# bat_mini_drby_viii.net
KiCad netlist of a schematic drawn in EAGLE
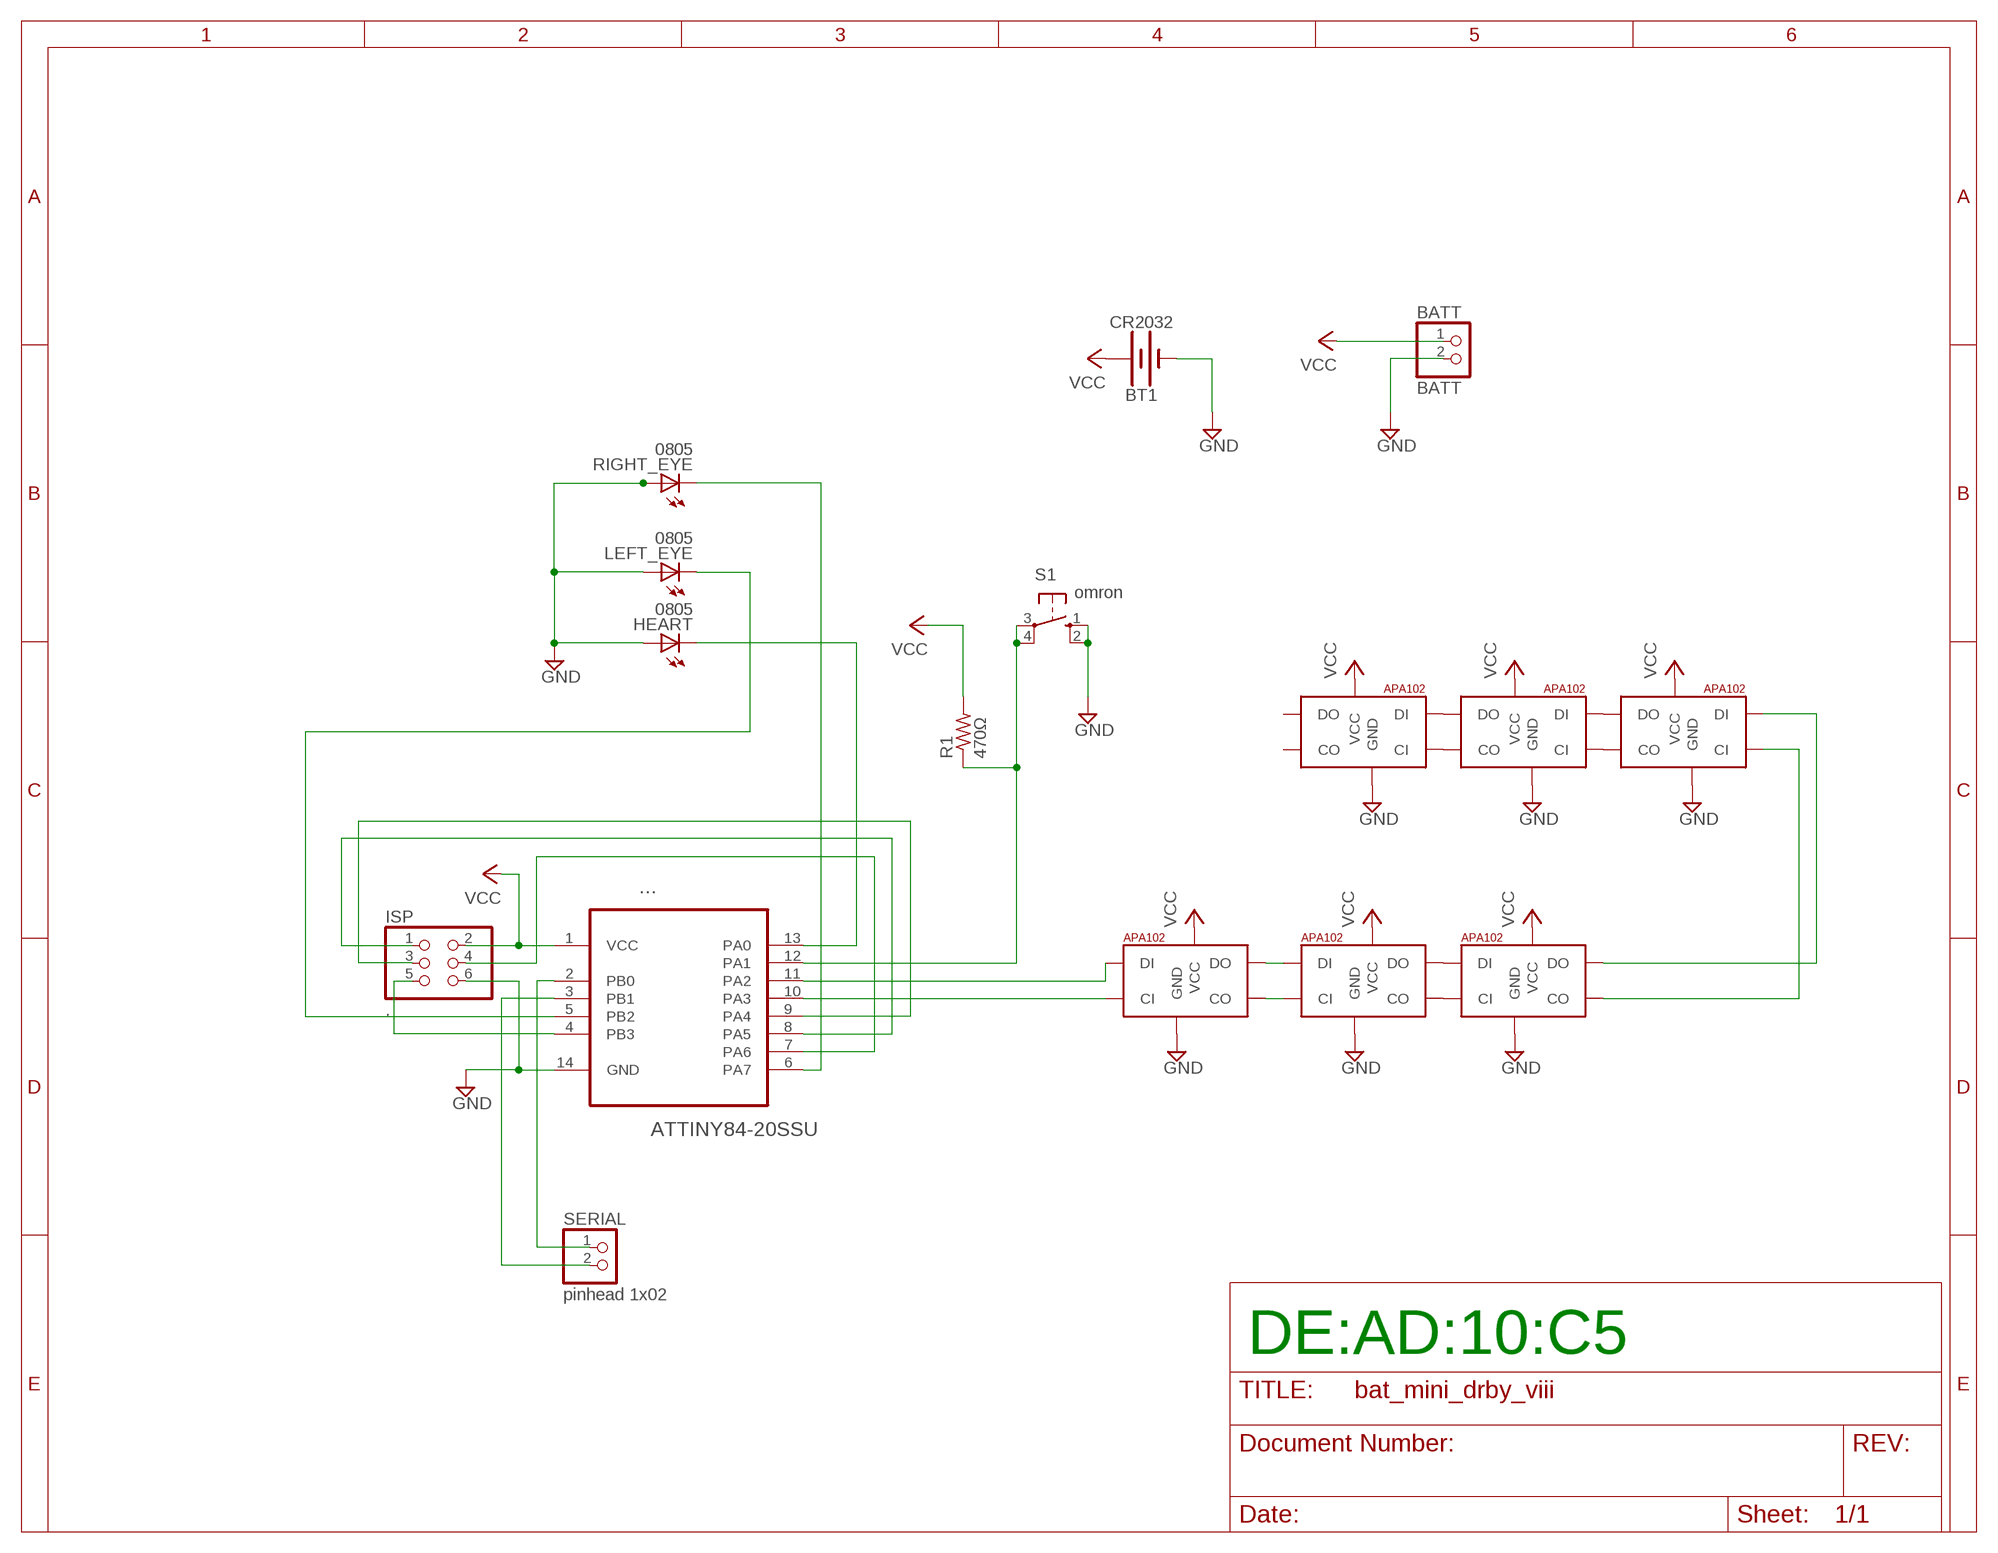
[diagram p0: schematic, sheet 1]

(export (version "E")
  (design (tool "Eeschema 10.0.6"))
  (components
    (comp (ref "...")
      (value "ATTINY84-20SSU")
      (footprint "eagle-import:SOIC127P600X175-14N")
      (libsource (lib "eagle-import") (part "ATTINY84-20SSU"))
    )
    (comp (ref "BATT")
      (value "BATT")
      (footprint "eagle-import:1X02")
      (libsource (lib "eagle-import") (part "PINHD-1X2"))
    )
    (comp (ref "BT1")
      (value "CR2032")
      (footprint "eagle-import:BATTCON_20MM_4LEGS")
      (libsource (lib "eagle-import") (part "BATTERY-20MM_SMD_4LEGS"))
    )
    (comp (ref "HEART")
      (value "0805")
      (footprint "eagle-import:CHIP-LED0805")
      (libsource (lib "eagle-import") (part "LEDCHIP-LED0805"))
    )
    (comp (ref "ISP")
      (value ".")
      (footprint "eagle-import:2X03")
      (libsource (lib "eagle-import") (part "PINHD-2X3"))
    )
    (comp (ref "LEFT_EYE")
      (value "0805")
      (footprint "eagle-import:CHIP-LED0805")
      (libsource (lib "eagle-import") (part "LEDCHIP-LED0805"))
    )
    (comp (ref "R1")
      (value "470Ω")
      (footprint "eagle-import:R0805")
      (libsource (lib "eagle-import") (part "R-US_R0805"))
    )
    (comp (ref "RIGHT_EYE")
      (value "0805")
      (footprint "eagle-import:CHIP-LED0805")
      (libsource (lib "eagle-import") (part "LEDCHIP-LED0805"))
    )
    (comp (ref "S1")
      (value "omron")
      (footprint "eagle-import:B3F-10XX")
      (fields (field (name "MPN") "B3F-1000"))
      (libsource (lib "eagle-import") (part "10-XX"))
    )
    (comp (ref "SERIAL")
      (value "pinhead 1x02")
      (footprint "eagle-import:1X02")
      (libsource (lib "eagle-import") (part "PINHD-1X2"))
    )
    (comp (ref "U$1")
      (value "APA1025050")
      (footprint "eagle-import:APA102_5050")
      (libsource (lib "eagle-import") (part "APA1025050"))
    )
    (comp (ref "U$2")
      (value "APA1025050")
      (footprint "eagle-import:APA102_5050")
      (libsource (lib "eagle-import") (part "APA1025050"))
    )
    (comp (ref "U$3")
      (value "APA1025050")
      (footprint "eagle-import:APA102_5050")
      (libsource (lib "eagle-import") (part "APA1025050"))
    )
    (comp (ref "U$5")
      (value "APA1025050")
      (footprint "eagle-import:APA102_5050")
      (libsource (lib "eagle-import") (part "APA1025050"))
    )
    (comp (ref "U$6")
      (value "APA1025050")
      (footprint "eagle-import:APA102_5050")
      (libsource (lib "eagle-import") (part "APA1025050"))
    )
    (comp (ref "U$7")
      (value "APA1025050")
      (footprint "eagle-import:APA102_5050")
      (libsource (lib "eagle-import") (part "APA1025050"))
    )
  )
  (nets
    (net (code "1") (name "GND") (class "Default")
      (node (ref "...") (pin "14") (pinfunction "GND_14") (pintype "passive"))
      (node (ref "BATT") (pin "2") (pinfunction "2_2") (pintype "passive"))
      (node (ref "BT1") (pin "NEGATIVE") (pinfunction "-_NEGATIVE") (pintype "power_in"))
      (node (ref "HEART") (pin "A") (pinfunction "A_A") (pintype "passive"))
      (node (ref "ISP") (pin "6") (pinfunction "6_6") (pintype "passive"))
      (node (ref "LEFT_EYE") (pin "A") (pinfunction "A_A") (pintype "passive"))
      (node (ref "RIGHT_EYE") (pin "A") (pinfunction "A_A") (pintype "passive"))
      (node (ref "S1") (pin "1") (pinfunction "S_1") (pintype "passive"))
      (node (ref "S1") (pin "2") (pinfunction "S1_2") (pintype "passive"))
      (node (ref "U$1") (pin "6") (pinfunction "GND_6") (pintype "bidirectional"))
      (node (ref "U$2") (pin "6") (pinfunction "GND_6") (pintype "bidirectional"))
      (node (ref "U$3") (pin "6") (pinfunction "GND_6") (pintype "bidirectional"))
      (node (ref "U$5") (pin "6") (pinfunction "GND_6") (pintype "bidirectional"))
      (node (ref "U$6") (pin "6") (pinfunction "GND_6") (pintype "bidirectional"))
      (node (ref "U$7") (pin "6") (pinfunction "GND_6") (pintype "bidirectional"))
    )
    (net (code "2") (name "Net-(...-PA0)") (class "Default")
      (node (ref "...") (pin "13") (pinfunction "PA0_13") (pintype "bidirectional"))
      (node (ref "HEART") (pin "C") (pinfunction "C_C") (pintype "passive"))
    )
    (net (code "3") (name "Net-(...-PA1)") (class "Default")
      (node (ref "...") (pin "12") (pinfunction "PA1_12") (pintype "bidirectional"))
      (node (ref "R1") (pin "1") (pinfunction "1_1") (pintype "passive"))
      (node (ref "S1") (pin "3") (pinfunction "P_3") (pintype "passive"))
      (node (ref "S1") (pin "4") (pinfunction "P1_4") (pintype "passive"))
    )
    (net (code "4") (name "Net-(...-PA2)") (class "Default")
      (node (ref "...") (pin "11") (pinfunction "PA2_11") (pintype "bidirectional"))
      (node (ref "U$1") (pin "4") (pinfunction "DI_4") (pintype "bidirectional"))
    )
    (net (code "5") (name "Net-(...-PA3)") (class "Default")
      (node (ref "...") (pin "10") (pinfunction "PA3_10") (pintype "bidirectional"))
      (node (ref "U$1") (pin "5") (pinfunction "CI_5") (pintype "bidirectional"))
    )
    (net (code "6") (name "Net-(...-PA4)") (class "Default")
      (node (ref "...") (pin "9") (pinfunction "PA4_9") (pintype "bidirectional"))
      (node (ref "ISP") (pin "3") (pinfunction "3_3") (pintype "passive"))
    )
    (net (code "7") (name "Net-(...-PA5)") (class "Default")
      (node (ref "...") (pin "8") (pinfunction "PA5_8") (pintype "bidirectional"))
      (node (ref "ISP") (pin "1") (pinfunction "1_1") (pintype "passive"))
    )
    (net (code "8") (name "Net-(...-PA6)") (class "Default")
      (node (ref "...") (pin "7") (pinfunction "PA6_7") (pintype "bidirectional"))
      (node (ref "ISP") (pin "4") (pinfunction "4_4") (pintype "passive"))
    )
    (net (code "9") (name "Net-(...-PA7)") (class "Default")
      (node (ref "...") (pin "6") (pinfunction "PA7_6") (pintype "bidirectional"))
      (node (ref "RIGHT_EYE") (pin "C") (pinfunction "C_C") (pintype "passive"))
    )
    (net (code "10") (name "Net-(...-PB0)") (class "Default")
      (node (ref "...") (pin "2") (pinfunction "PB0_2") (pintype "bidirectional"))
      (node (ref "SERIAL") (pin "1") (pinfunction "1_1") (pintype "passive"))
    )
    (net (code "11") (name "Net-(...-PB1)") (class "Default")
      (node (ref "...") (pin "3") (pinfunction "PB1_3") (pintype "bidirectional"))
      (node (ref "SERIAL") (pin "2") (pinfunction "2_2") (pintype "passive"))
    )
    (net (code "12") (name "Net-(...-PB2)") (class "Default")
      (node (ref "...") (pin "5") (pinfunction "PB2_5") (pintype "bidirectional"))
      (node (ref "LEFT_EYE") (pin "C") (pinfunction "C_C") (pintype "passive"))
    )
    (net (code "13") (name "Net-(...-PB3)") (class "Default")
      (node (ref "...") (pin "4") (pinfunction "PB3_4") (pintype "bidirectional"))
      (node (ref "ISP") (pin "5") (pinfunction "5_5") (pintype "passive"))
    )
    (net (code "14") (name "Net-(U$1-CO)") (class "Default")
      (node (ref "U$1") (pin "2") (pinfunction "CO_2") (pintype "bidirectional"))
      (node (ref "U$2") (pin "5") (pinfunction "CI_5") (pintype "bidirectional"))
    )
    (net (code "15") (name "Net-(U$1-DO)") (class "Default")
      (node (ref "U$1") (pin "3") (pinfunction "DO_3") (pintype "bidirectional"))
      (node (ref "U$2") (pin "4") (pinfunction "DI_4") (pintype "bidirectional"))
    )
    (net (code "16") (name "Net-(U$2-CO)") (class "Default")
      (node (ref "U$2") (pin "2") (pinfunction "CO_2") (pintype "bidirectional"))
      (node (ref "U$3") (pin "5") (pinfunction "CI_5") (pintype "bidirectional"))
    )
    (net (code "17") (name "Net-(U$2-DO)") (class "Default")
      (node (ref "U$2") (pin "3") (pinfunction "DO_3") (pintype "bidirectional"))
      (node (ref "U$3") (pin "4") (pinfunction "DI_4") (pintype "bidirectional"))
    )
    (net (code "18") (name "Net-(U$3-CO)") (class "Default")
      (node (ref "U$3") (pin "2") (pinfunction "CO_2") (pintype "bidirectional"))
      (node (ref "U$5") (pin "5") (pinfunction "CI_5") (pintype "bidirectional"))
    )
    (net (code "19") (name "Net-(U$3-DO)") (class "Default")
      (node (ref "U$3") (pin "3") (pinfunction "DO_3") (pintype "bidirectional"))
      (node (ref "U$5") (pin "4") (pinfunction "DI_4") (pintype "bidirectional"))
    )
    (net (code "20") (name "Net-(U$5-CO)") (class "Default")
      (node (ref "U$5") (pin "2") (pinfunction "CO_2") (pintype "bidirectional"))
      (node (ref "U$6") (pin "5") (pinfunction "CI_5") (pintype "bidirectional"))
    )
    (net (code "21") (name "Net-(U$5-DO)") (class "Default")
      (node (ref "U$5") (pin "3") (pinfunction "DO_3") (pintype "bidirectional"))
      (node (ref "U$6") (pin "4") (pinfunction "DI_4") (pintype "bidirectional"))
    )
    (net (code "22") (name "Net-(U$6-CO)") (class "Default")
      (node (ref "U$6") (pin "2") (pinfunction "CO_2") (pintype "bidirectional"))
      (node (ref "U$7") (pin "5") (pinfunction "CI_5") (pintype "bidirectional"))
    )
    (net (code "23") (name "Net-(U$6-DO)") (class "Default")
      (node (ref "U$6") (pin "3") (pinfunction "DO_3") (pintype "bidirectional"))
      (node (ref "U$7") (pin "4") (pinfunction "DI_4") (pintype "bidirectional"))
    )
    (net (code "24") (name "VCC") (class "Default")
      (node (ref "...") (pin "1") (pinfunction "VCC_1") (pintype "power_in"))
      (node (ref "BATT") (pin "1") (pinfunction "1_1") (pintype "passive"))
      (node (ref "BT1") (pin "POSITIVE@1") (pinfunction "+_POSITIVE@1") (pintype "power_in"))
      (node (ref "BT1") (pin "POSITIVE@2") (pinfunction "+_POSITIVE@2") (pintype "power_in"))
      (node (ref "BT1") (pin "POSITIVE@3") (pinfunction "+_POSITIVE@3") (pintype "power_in"))
      (node (ref "BT1") (pin "POSITIVE@4") (pinfunction "+_POSITIVE@4") (pintype "power_in"))
      (node (ref "ISP") (pin "2") (pinfunction "2_2") (pintype "passive"))
      (node (ref "R1") (pin "2") (pinfunction "2_2") (pintype "passive"))
      (node (ref "U$1") (pin "1") (pinfunction "VCC_1") (pintype "bidirectional"))
      (node (ref "U$2") (pin "1") (pinfunction "VCC_1") (pintype "bidirectional"))
      (node (ref "U$3") (pin "1") (pinfunction "VCC_1") (pintype "bidirectional"))
      (node (ref "U$5") (pin "1") (pinfunction "VCC_1") (pintype "bidirectional"))
      (node (ref "U$6") (pin "1") (pinfunction "VCC_1") (pintype "bidirectional"))
      (node (ref "U$7") (pin "1") (pinfunction "VCC_1") (pintype "bidirectional"))
    )
    (net (code "25") (name "unconnected-(U$7-CO-Pad2)") (class "Default")
      (node (ref "U$7") (pin "2") (pinfunction "CO_2") (pintype "bidirectional"))
    )
    (net (code "26") (name "unconnected-(U$7-DO-Pad3)") (class "Default")
      (node (ref "U$7") (pin "3") (pinfunction "DO_3") (pintype "bidirectional"))
    )
  )
)
